# SD_Handler.net
KiCad netlist of a schematic drawn in EAGLE
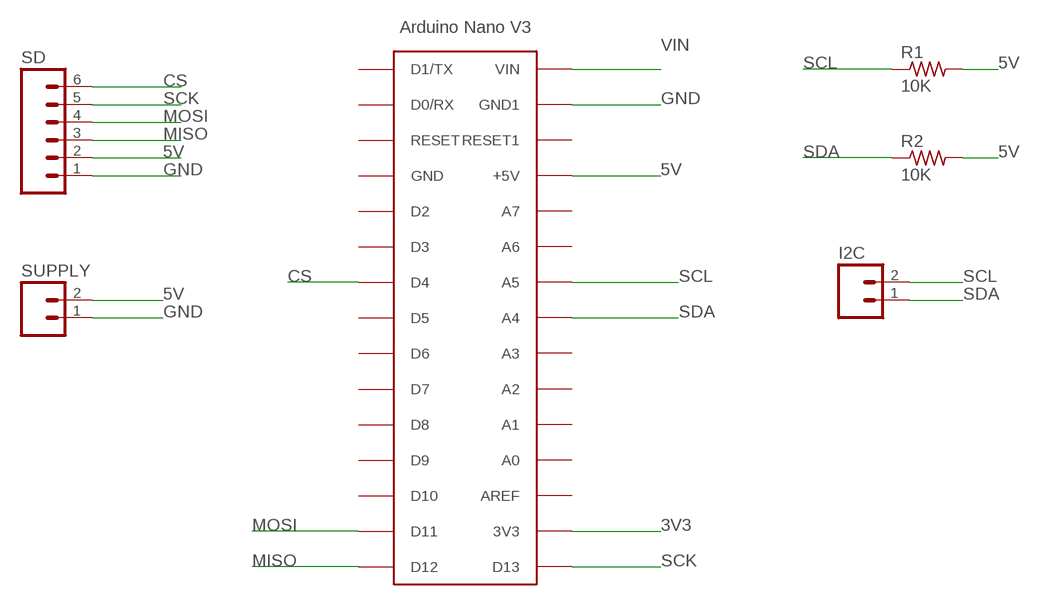
[diagram p0: schematic, sheet 1]

(export (version "E")
  (design (tool "Eeschema 10.0.6"))
  (components
    (comp (ref "I2C")
      (value "M02")
      (footprint "eagle-import:02P")
      (libsource (lib "eagle-import") (part "M02"))
    )
    (comp (ref "R1")
      (value "10K")
      (footprint "eagle-import:0207_10")
      (libsource (lib "eagle-import") (part "R-US_0207/10"))
    )
    (comp (ref "R2")
      (value "10K")
      (footprint "eagle-import:0207_10")
      (libsource (lib "eagle-import") (part "R-US_0207/10"))
    )
    (comp (ref "SD")
      (value "M06LONGPADS")
      (footprint "eagle-import:1X06_LONGPADS")
      (libsource (lib "eagle-import") (part "M06LONGPADS"))
    )
    (comp (ref "SUPPLY")
      (value "M02")
      (footprint "eagle-import:02P")
      (libsource (lib "eagle-import") (part "M02"))
    )
    (comp (ref "U$1")
      (value "ARDUINONANO")
      (footprint "eagle-import:PDIP-32")
      (libsource (lib "eagle-import") (part "ARDUINONANO"))
    )
  )
  (nets
    (net (code "1") (name "/3V3") (class "Default")
      (node (ref "U$1") (pin "3V3") (pinfunction "3V3_3V3") (pintype "bidirectional"))
    )
    (net (code "2") (name "/5V") (class "Default")
      (node (ref "R1") (pin "2") (pinfunction "2_2") (pintype "passive"))
      (node (ref "R2") (pin "2") (pinfunction "2_2") (pintype "passive"))
      (node (ref "SD") (pin "2") (pinfunction "2_2") (pintype "passive"))
      (node (ref "SUPPLY") (pin "2") (pinfunction "2_2") (pintype "passive"))
      (node (ref "U$1") (pin "+5V") (pinfunction "+5V_+5V") (pintype "bidirectional"))
    )
    (net (code "3") (name "/CS") (class "Default")
      (node (ref "SD") (pin "6") (pinfunction "6_6") (pintype "passive"))
      (node (ref "U$1") (pin "D4") (pinfunction "D4_D4") (pintype "bidirectional"))
    )
    (net (code "4") (name "/GND") (class "Default")
      (node (ref "SD") (pin "1") (pinfunction "1_1") (pintype "passive"))
      (node (ref "SUPPLY") (pin "1") (pinfunction "1_1") (pintype "passive"))
      (node (ref "U$1") (pin "GND1") (pinfunction "GND1_GND1") (pintype "bidirectional"))
    )
    (net (code "5") (name "/MISO") (class "Default")
      (node (ref "SD") (pin "3") (pinfunction "3_3") (pintype "passive"))
      (node (ref "U$1") (pin "D12") (pinfunction "D12_D12") (pintype "bidirectional"))
    )
    (net (code "6") (name "/MOSI") (class "Default")
      (node (ref "SD") (pin "4") (pinfunction "4_4") (pintype "passive"))
      (node (ref "U$1") (pin "D11") (pinfunction "D11_D11") (pintype "bidirectional"))
    )
    (net (code "7") (name "/SCK") (class "Default")
      (node (ref "SD") (pin "5") (pinfunction "5_5") (pintype "passive"))
      (node (ref "U$1") (pin "D13") (pinfunction "D13_D13") (pintype "bidirectional"))
    )
    (net (code "8") (name "/SCL") (class "Default")
      (node (ref "I2C") (pin "2") (pinfunction "2_2") (pintype "passive"))
      (node (ref "R1") (pin "1") (pinfunction "1_1") (pintype "passive"))
      (node (ref "U$1") (pin "A2") (pinfunction "A5_A2") (pintype "bidirectional"))
    )
    (net (code "9") (name "/SDA") (class "Default")
      (node (ref "I2C") (pin "1") (pinfunction "1_1") (pintype "passive"))
      (node (ref "R2") (pin "1") (pinfunction "1_1") (pintype "passive"))
      (node (ref "U$1") (pin "A3") (pinfunction "A4_A3") (pintype "bidirectional"))
    )
    (net (code "10") (name "/VIN") (class "Default")
      (node (ref "U$1") (pin "VIN") (pinfunction "VIN_VIN") (pintype "bidirectional"))
    )
    (net (code "11") (name "unconnected-(U$1-A0-PadA7)") (class "Default")
      (node (ref "U$1") (pin "A7") (pinfunction "A0_A7") (pintype "bidirectional"))
    )
    (net (code "12") (name "unconnected-(U$1-A1-PadA6)") (class "Default")
      (node (ref "U$1") (pin "A6") (pinfunction "A1_A6") (pintype "bidirectional"))
    )
    (net (code "13") (name "unconnected-(U$1-A2-PadA5)") (class "Default")
      (node (ref "U$1") (pin "A5") (pinfunction "A2_A5") (pintype "bidirectional"))
    )
    (net (code "14") (name "unconnected-(U$1-A3-PadA4)") (class "Default")
      (node (ref "U$1") (pin "A4") (pinfunction "A3_A4") (pintype "bidirectional"))
    )
    (net (code "15") (name "unconnected-(U$1-A6-PadA1)") (class "Default")
      (node (ref "U$1") (pin "A1") (pinfunction "A6_A1") (pintype "bidirectional"))
    )
    (net (code "16") (name "unconnected-(U$1-A7-PadA0)") (class "Default")
      (node (ref "U$1") (pin "A0") (pinfunction "A7_A0") (pintype "bidirectional"))
    )
    (net (code "17") (name "unconnected-(U$1-PadAREF)") (class "Default")
      (node (ref "U$1") (pin "AREF") (pinfunction "AREF_AREF") (pintype "bidirectional"))
    )
    (net (code "18") (name "unconnected-(U$1-PadD0{slash}RX)") (class "Default")
      (node (ref "U$1") (pin "D0/RX") (pinfunction "D0/RX_D0/RX") (pintype "bidirectional"))
    )
    (net (code "19") (name "unconnected-(U$1-PadD1{slash}TX)") (class "Default")
      (node (ref "U$1") (pin "D1/TX") (pinfunction "D1/TX_D1/TX") (pintype "bidirectional"))
    )
    (net (code "20") (name "unconnected-(U$1-PadD2)") (class "Default")
      (node (ref "U$1") (pin "D2") (pinfunction "D2_D2") (pintype "bidirectional"))
    )
    (net (code "21") (name "unconnected-(U$1-PadD3)") (class "Default")
      (node (ref "U$1") (pin "D3") (pinfunction "D3_D3") (pintype "bidirectional"))
    )
    (net (code "22") (name "unconnected-(U$1-PadD5)") (class "Default")
      (node (ref "U$1") (pin "D5") (pinfunction "D5_D5") (pintype "bidirectional"))
    )
    (net (code "23") (name "unconnected-(U$1-PadD6)") (class "Default")
      (node (ref "U$1") (pin "D6") (pinfunction "D6_D6") (pintype "bidirectional"))
    )
    (net (code "24") (name "unconnected-(U$1-PadD7)") (class "Default")
      (node (ref "U$1") (pin "D7") (pinfunction "D7_D7") (pintype "bidirectional"))
    )
    (net (code "25") (name "unconnected-(U$1-PadD8)") (class "Default")
      (node (ref "U$1") (pin "D8") (pinfunction "D8_D8") (pintype "bidirectional"))
    )
    (net (code "26") (name "unconnected-(U$1-PadD9)") (class "Default")
      (node (ref "U$1") (pin "D9") (pinfunction "D9_D9") (pintype "bidirectional"))
    )
    (net (code "27") (name "unconnected-(U$1-PadD10)") (class "Default")
      (node (ref "U$1") (pin "D10") (pinfunction "D10_D10") (pintype "bidirectional"))
    )
    (net (code "28") (name "unconnected-(U$1-PadGND)") (class "Default")
      (node (ref "U$1") (pin "GND") (pinfunction "GND_GND") (pintype "bidirectional"))
    )
    (net (code "29") (name "unconnected-(U$1-PadRESET)") (class "Default")
      (node (ref "U$1") (pin "RESET") (pinfunction "RESET_RESET") (pintype "bidirectional"))
    )
    (net (code "30") (name "unconnected-(U$1-PadRESET1)") (class "Default")
      (node (ref "U$1") (pin "RESET1") (pinfunction "RESET1_RESET1") (pintype "bidirectional"))
    )
  )
)
